# DM1097_MIPI_IO.net
KiCad netlist of a schematic drawn in Altium Designer
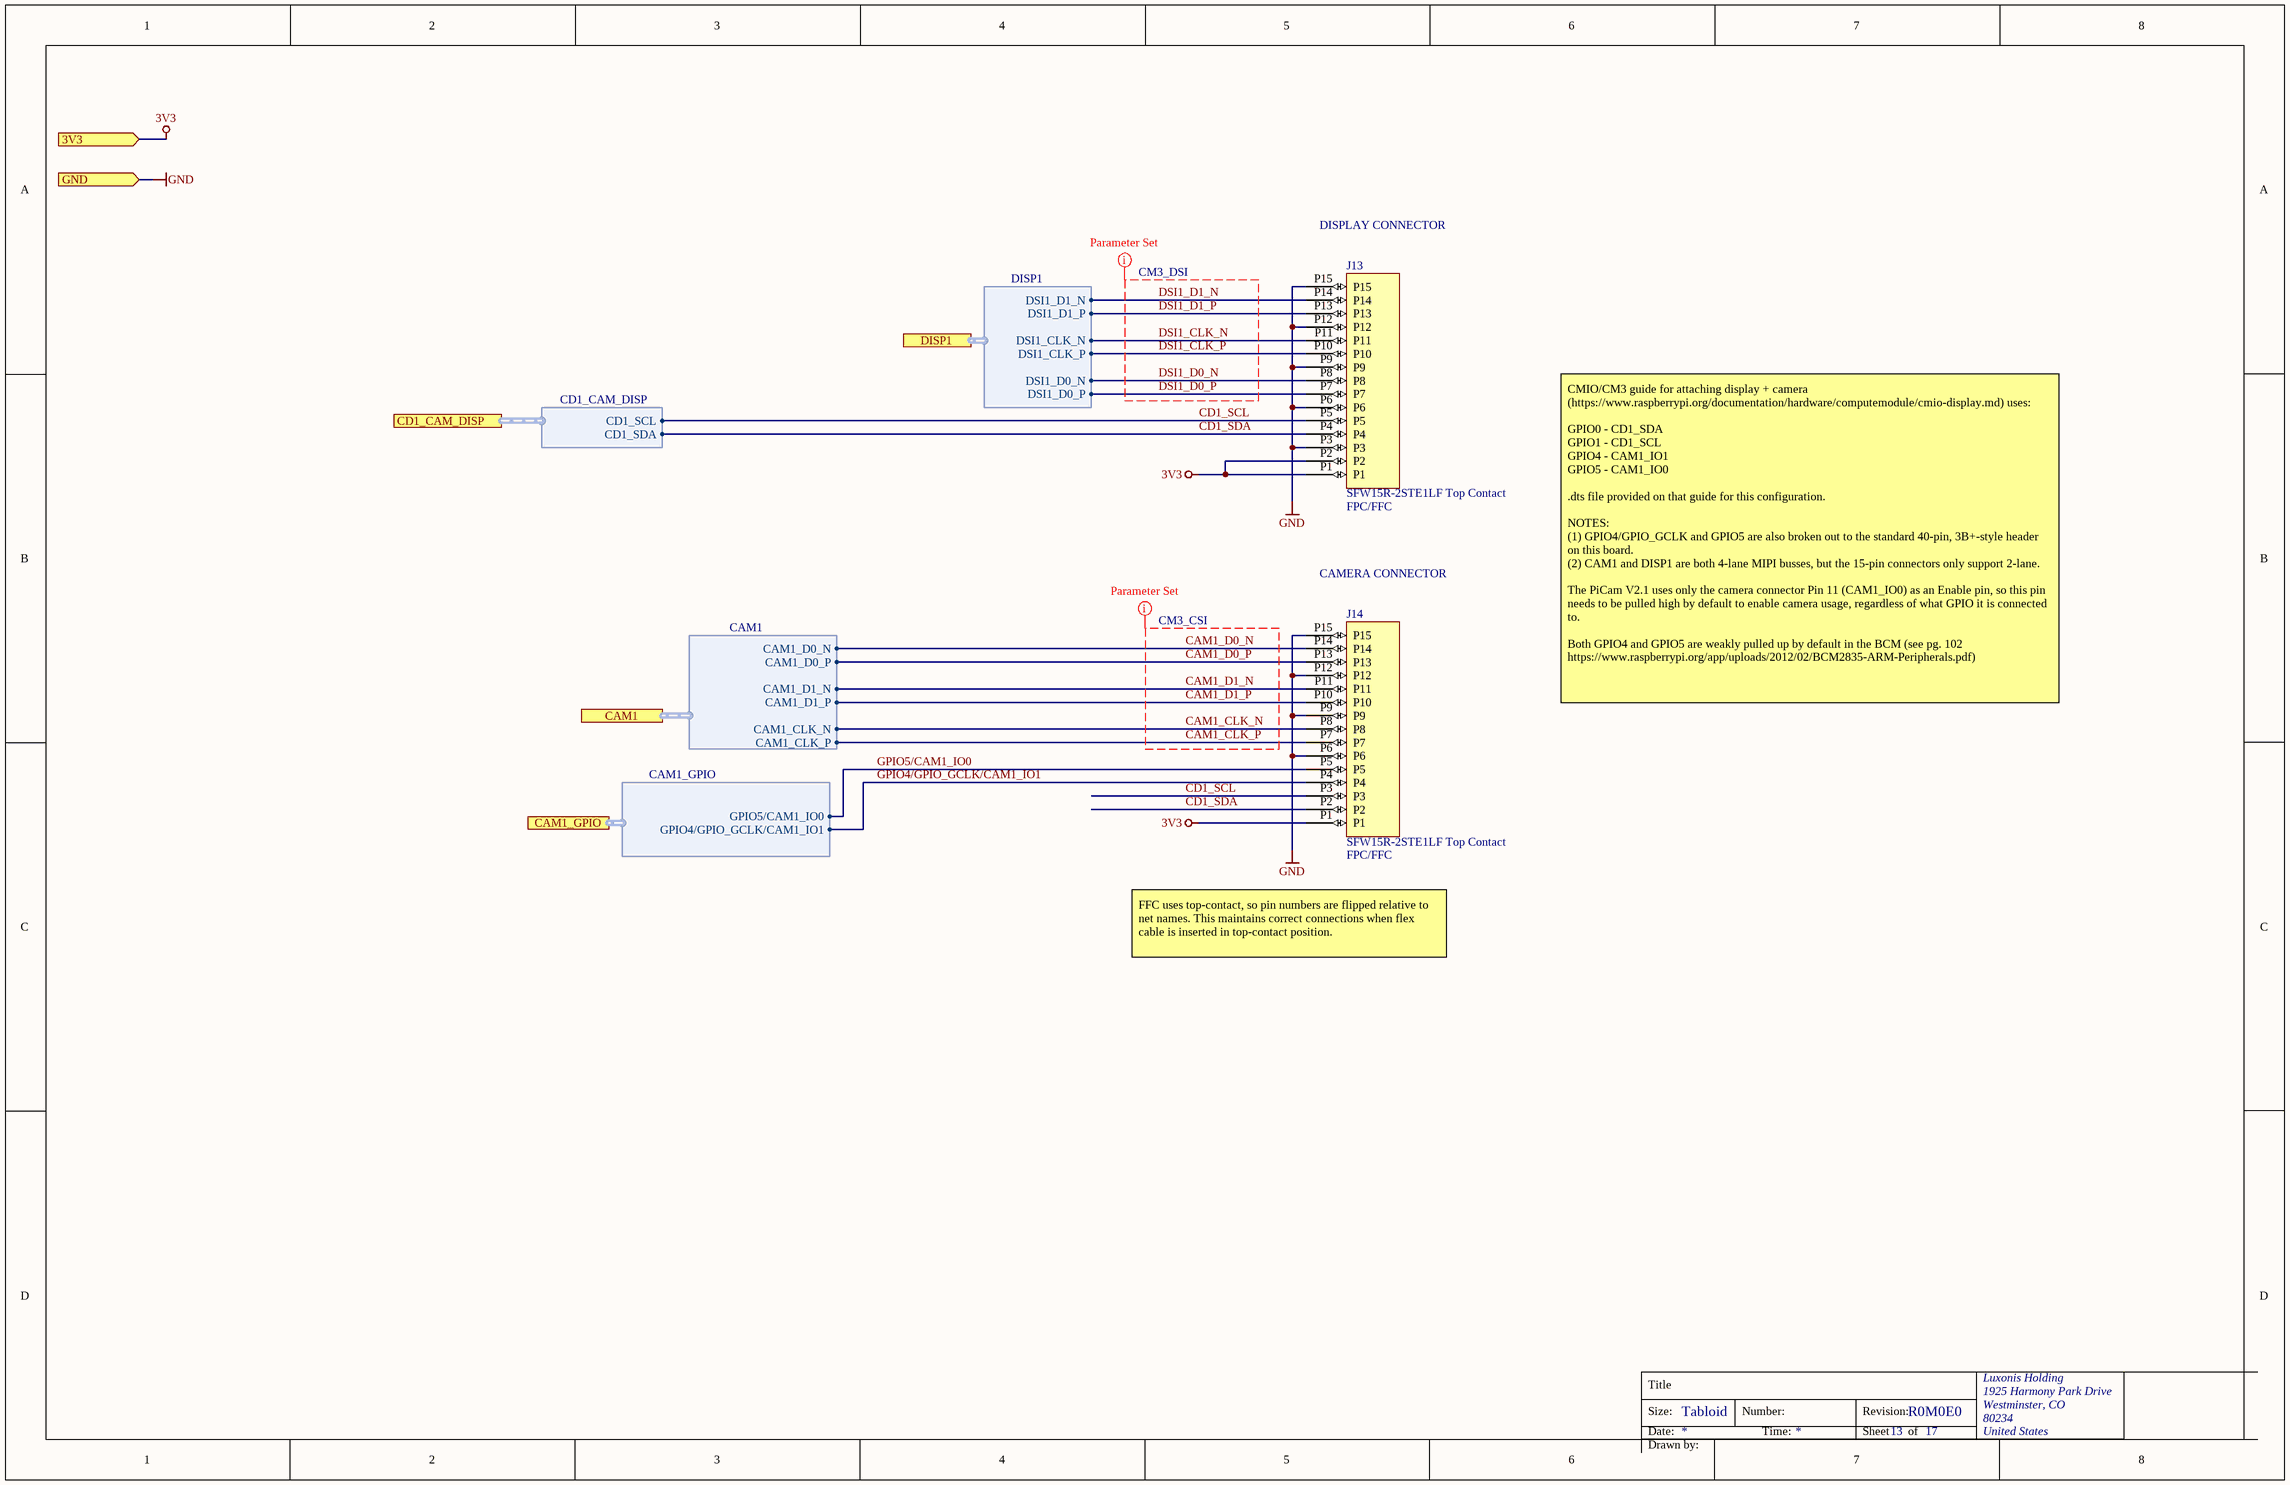
[diagram p0: DM1097_MIPI_IO.SchDoc]

(export (version "E")
  (design (tool "Eeschema 10.0.6"))
  (components
    (comp (ref "J13")
      (value "SFW15R-2STE1LF Top Contact")
      (footprint "LuxonisMaster:SFW15R-2STE1LF")
      (description "CONN FFC FPC TOP 15POS 1MM R/A")
      (fields (field (name "MANUFACTURER") "Amphenol") (field (name "COMPONENT SUBTYPE") "FPC/FFC"))
      (libsource (lib "LuxonisMaster") (part "SFW15R-2STE1LF"))
    )
    (comp (ref "J14")
      (value "SFW15R-2STE1LF Top Contact")
      (footprint "LuxonisMaster:SFW15R-2STE1LF")
      (description "CONN FFC FPC TOP 15POS 1MM R/A")
      (fields (field (name "MANUFACTURER") "Amphenol") (field (name "COMPONENT SUBTYPE") "FPC/FFC"))
      (libsource (lib "LuxonisMaster") (part "SFW15R-2STE1LF"))
    )
  )
  (nets
    (net (code "5") (name "/CAM1_CLK_N") (class "Default")
      (node (ref "J14") (pin "P8") (pinfunction "P8_P8") (pintype "bidirectional"))
    )
    (net (code "6") (name "/CAM1_CLK_P") (class "Default")
      (node (ref "J14") (pin "P7") (pinfunction "P7_P7") (pintype "bidirectional"))
    )
    (net (code "7") (name "/CAM1_D0_N") (class "Default")
      (node (ref "J14") (pin "P14") (pinfunction "P14_P14") (pintype "bidirectional"))
    )
    (net (code "8") (name "/CAM1_D0_P") (class "Default")
      (node (ref "J14") (pin "P13") (pinfunction "P13_P13") (pintype "bidirectional"))
    )
    (net (code "9") (name "/CAM1_D1_N") (class "Default")
      (node (ref "J14") (pin "P11") (pinfunction "P11_P11") (pintype "bidirectional"))
    )
    (net (code "10") (name "/CAM1_D1_P") (class "Default")
      (node (ref "J14") (pin "P10") (pinfunction "P10_P10") (pintype "bidirectional"))
    )
    (net (code "11") (name "/CD1_SCL") (class "Default")
      (node (ref "J13") (pin "P5") (pinfunction "P5_P5") (pintype "bidirectional"))
      (node (ref "J14") (pin "P3") (pinfunction "P3_P3") (pintype "bidirectional"))
    )
    (net (code "12") (name "/CD1_SDA") (class "Default")
      (node (ref "J13") (pin "P4") (pinfunction "P4_P4") (pintype "bidirectional"))
      (node (ref "J14") (pin "P2") (pinfunction "P2_P2") (pintype "bidirectional"))
    )
    (net (code "13") (name "/DSI1_CLK_N") (class "Default")
      (node (ref "J13") (pin "P11") (pinfunction "P11_P11") (pintype "bidirectional"))
    )
    (net (code "14") (name "/DSI1_CLK_P") (class "Default")
      (node (ref "J13") (pin "P10") (pinfunction "P10_P10") (pintype "bidirectional"))
    )
    (net (code "15") (name "/DSI1_D0_N") (class "Default")
      (node (ref "J13") (pin "P8") (pinfunction "P8_P8") (pintype "bidirectional"))
    )
    (net (code "16") (name "/DSI1_D0_P") (class "Default")
      (node (ref "J13") (pin "P7") (pinfunction "P7_P7") (pintype "bidirectional"))
    )
    (net (code "17") (name "/DSI1_D1_N") (class "Default")
      (node (ref "J13") (pin "P14") (pinfunction "P14_P14") (pintype "bidirectional"))
    )
    (net (code "18") (name "/DSI1_D1_P") (class "Default")
      (node (ref "J13") (pin "P13") (pinfunction "P13_P13") (pintype "bidirectional"))
    )
    (net (code "19") (name "/GPIO4{slash}GPIO_GCLK{slash}CAM1_IO1") (class "Default")
      (node (ref "J14") (pin "P4") (pinfunction "P4_P4") (pintype "bidirectional"))
    )
    (net (code "20") (name "/GPIO5{slash}CAM1_IO0") (class "Default")
      (node (ref "J14") (pin "P5") (pinfunction "P5_P5") (pintype "bidirectional"))
    )
    (net (code "25") (name "3V3") (class "Default")
      (node (ref "J13") (pin "P1") (pinfunction "P1_P1") (pintype "bidirectional"))
      (node (ref "J13") (pin "P2") (pinfunction "P2_P2") (pintype "bidirectional"))
      (node (ref "J14") (pin "P1") (pinfunction "P1_P1") (pintype "bidirectional"))
    )
    (net (code "26") (name "GND") (class "Default")
      (node (ref "J13") (pin "P12") (pinfunction "P12_P12") (pintype "bidirectional"))
      (node (ref "J13") (pin "P15") (pinfunction "P15_P15") (pintype "bidirectional"))
      (node (ref "J13") (pin "P3") (pinfunction "P3_P3") (pintype "bidirectional"))
      (node (ref "J13") (pin "P6") (pinfunction "P6_P6") (pintype "bidirectional"))
      (node (ref "J13") (pin "P9") (pinfunction "P9_P9") (pintype "bidirectional"))
      (node (ref "J14") (pin "P12") (pinfunction "P12_P12") (pintype "bidirectional"))
      (node (ref "J14") (pin "P15") (pinfunction "P15_P15") (pintype "bidirectional"))
      (node (ref "J14") (pin "P6") (pinfunction "P6_P6") (pintype "bidirectional"))
      (node (ref "J14") (pin "P9") (pinfunction "P9_P9") (pintype "bidirectional"))
    )
  )
)
